# Power.net
KiCad netlist of a schematic drawn in Altium Designer
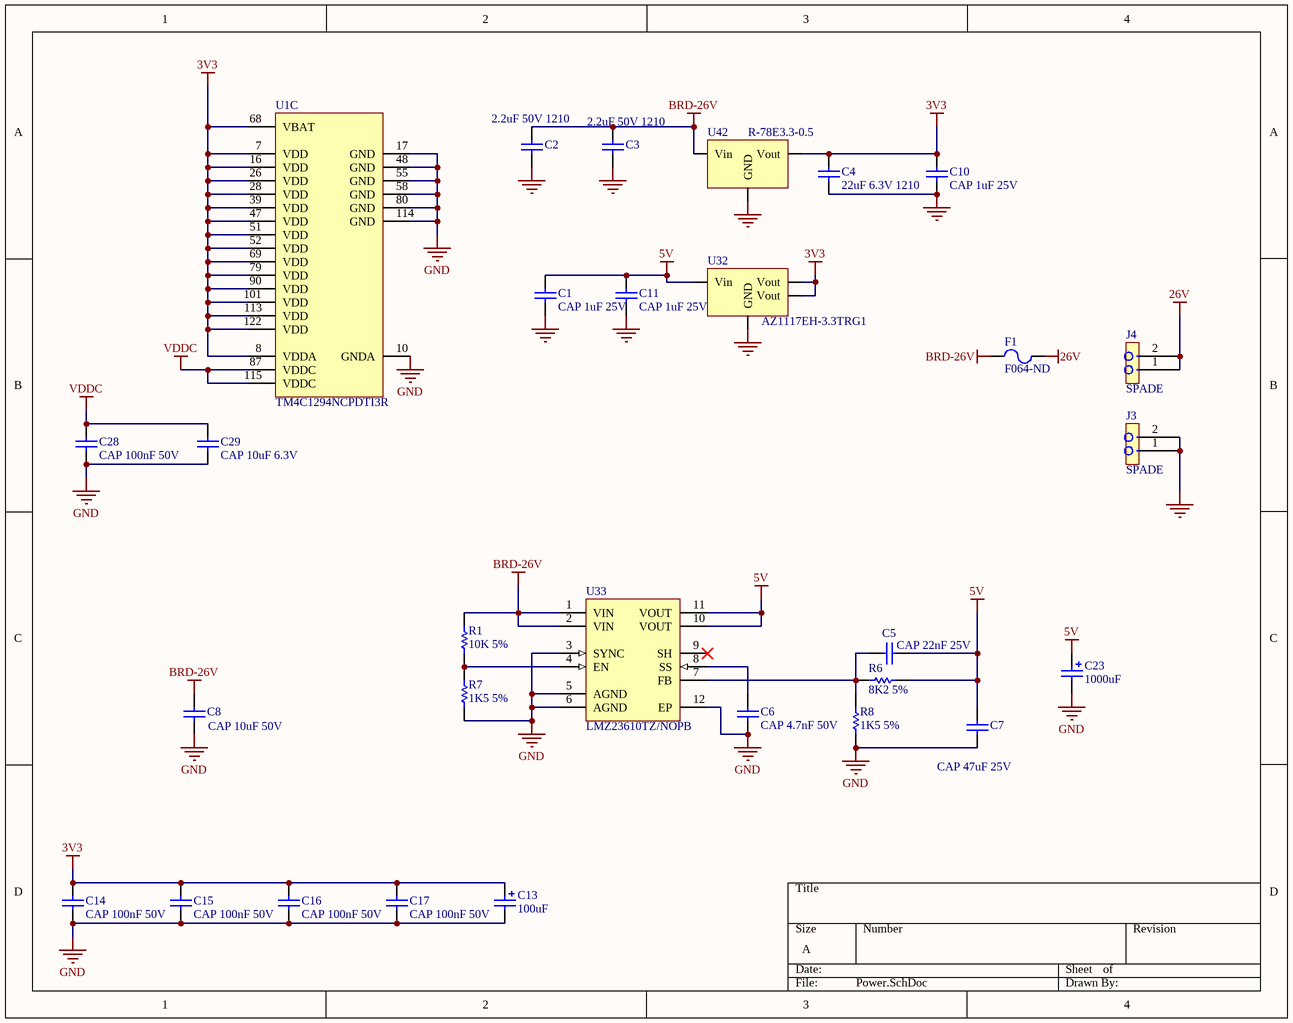
[diagram p0: Power.SchDoc]

(export (version "E")
  (design (tool "Eeschema 10.0.6"))
  (components
    (comp (ref "C1")
      (value "CAP 1uF 25V")
      (footprint "CAPC0603(1608)100_M")
      (description "CAP 1uF 25V Â±0.25pF 0603 (1608 Metric) Thickness 1mm SMD")
      (fields (field (name "TOLERANCE") "Â±0.25pF"))
      (libsource (lib "Altium Content Vault") (part "CMP-1035-00037-1"))
    )
    (comp (ref "C2")
      (value "2.2uF 50V 1210")
      (footprint "CAPC1210(3225)280_M")
      (description "CAP 2.2uF 50V ±20% 1210 (3225 Metric) Thickness 2.8mm SMD")
      (fields (field (name "TOLERANCE") "Â±20%"))
      (libsource (lib "Altium Content Vault") (part "CAP"))
    )
    (comp (ref "C3")
      (value "2.2uF 50V 1210")
      (footprint "CAPC1210(3225)280_M")
      (description "CAP 2.2uF 50V ±20% 1210 (3225 Metric) Thickness 2.8mm SMD")
      (fields (field (name "TOLERANCE") "Â±20%"))
      (libsource (lib "Altium Content Vault") (part "CAP"))
    )
    (comp (ref "C4")
      (value "22uF 6.3V 1210")
      (footprint "CAPC1210(3225)220_N")
      (description "CAP 22uF 6.3V ±10% 1210 (3225 Metric) Thickness 2.2mm SMD")
      (fields (field (name "TOLERANCE") "Â±10%"))
      (libsource (lib "Altium Content Vault") (part "CAP"))
    )
    (comp (ref "C5")
      (value "CAP 22nF 25V")
      (footprint "CAPC0805(2012)100_M")
      (description "CAP 22nF 25V Â±5% 0805 (2012 Metric) Thickness 1mm SMD")
      (fields (field (name "TOLERANCE") "Â±5%"))
      (libsource (lib "Altium Content Vault") (part "CMP-1036-04051-1"))
    )
    (comp (ref "C6")
      (value "CAP 4.7nF 50V")
      (footprint "CAPC0603(1608)100_M")
      (description "CAP 4.7nF 50V Â±20% 0603 (1608 Metric) Thickness 1mm SMD")
      (fields (field (name "TOLERANCE") "Â±20%"))
      (libsource (lib "Altium Content Vault") (part "CMP-1035-00333-1"))
    )
    (comp (ref "C7")
      (value "CAP 47uF 25V")
      (footprint "CAPC1206(3216)100_L")
      (description "CAP 47uF 25V Â±0.25pF 1206 (3216 Metric) Thickness 1mm SMD")
      (fields (field (name "TOLERANCE") "Â±0.25pF"))
      (libsource (lib "Altium Content Vault") (part "CMP-1037-00376-1"))
    )
    (comp (ref "C8")
      (value "CAP 10uF 50V")
      (footprint "CAPC1206(3216)190_M")
      (description "CAP 10uF 50V Â±10% 1206 (3216 Metric) Thickness 1.9mm SMD")
      (fields (field (name "TOLERANCE") "Â±10%"))
      (libsource (lib "Altium Content Vault") (part "CMP-1037-04982-1"))
    )
    (comp (ref "C10")
      (value "CAP 1uF 25V")
      (footprint "CAPC0603(1608)100_M")
      (description "CAP 1uF 25V Â±0.25pF 0603 (1608 Metric) Thickness 1mm SMD")
      (fields (field (name "TOLERANCE") "Â±0.25pF"))
      (libsource (lib "Altium Content Vault") (part "CMP-1035-00037-1"))
    )
    (comp (ref "C11")
      (value "CAP 1uF 25V")
      (footprint "CAPC0603(1608)100_M")
      (description "CAP 1uF 25V Â±0.25pF 0603 (1608 Metric) Thickness 1mm SMD")
      (fields (field (name "TOLERANCE") "Â±0.25pF"))
      (libsource (lib "Altium Content Vault") (part "CMP-1035-00037-1"))
    )
    (comp (ref "C13")
      (value "100uF")
      (footprint "PANASONIC_C")
      (description "Polarized Capacitor (Surface Mount)")
      (fields (field (name "PUBLISHER") "Altium Limited"))
      (libsource (lib "snarc+") (part "Cap_Polarized_100uF"))
    )
    (comp (ref "C14")
      (value "CAP 100nF 50V")
      (footprint "CAPC0603(1608)100_M")
      (description "CAP 100nF 50V Â±0.1pF 0603 (1608 Metric) Thickness 1mm SMD")
      (fields (field (name "TOLERANCE") "Â±0.1pF"))
      (libsource (lib "Altium Content Vault") (part "CMP-1035-00010-1"))
    )
    (comp (ref "C15")
      (value "CAP 100nF 50V")
      (footprint "CAPC0603(1608)100_M")
      (description "CAP 100nF 50V Â±0.1pF 0603 (1608 Metric) Thickness 1mm SMD")
      (fields (field (name "TOLERANCE") "Â±0.1pF"))
      (libsource (lib "Altium Content Vault") (part "CMP-1035-00010-1"))
    )
    (comp (ref "C16")
      (value "CAP 100nF 50V")
      (footprint "CAPC0603(1608)100_M")
      (description "CAP 100nF 50V Â±0.1pF 0603 (1608 Metric) Thickness 1mm SMD")
      (fields (field (name "TOLERANCE") "Â±0.1pF"))
      (libsource (lib "Altium Content Vault") (part "CMP-1035-00010-1"))
    )
    (comp (ref "C17")
      (value "CAP 100nF 50V")
      (footprint "CAPC0603(1608)100_M")
      (description "CAP 100nF 50V Â±0.1pF 0603 (1608 Metric) Thickness 1mm SMD")
      (fields (field (name "TOLERANCE") "Â±0.1pF"))
      (libsource (lib "Altium Content Vault") (part "CMP-1035-00010-1"))
    )
    (comp (ref "C23")
      (value "1000uF")
      (footprint "PANASONIC_H13")
      (description "Polarized Capacitor (Surface Mount)")
      (fields (field (name "PUBLISHER") "Altium Limited"))
      (libsource (lib "snarc+") (part "Cap_Polarized_1000uF"))
    )
    (comp (ref "C28")
      (value "CAP 100nF 50V")
      (footprint "CAPC0603(1608)100_M")
      (description "CAP 100nF 50V Â±0.1pF 0603 (1608 Metric) Thickness 1mm SMD")
      (fields (field (name "TOLERANCE") "Â±0.1pF"))
      (libsource (lib "Altium Content Vault") (part "CMP-1035-00010-1"))
    )
    (comp (ref "C29")
      (value "CAP 10uF 6.3V")
      (footprint "CAPC0603(1608)100_M")
      (description "CAP 10uF 6.3V ±10% 0603 (1608 Metric) Thickness 1mm SMD")
      (fields (field (name "TOLERANCE") "Â±10%"))
      (libsource (lib "Altium Content Vault") (part "CMP-1035-02796-1"))
    )
    (comp (ref "F1")
      (value "FUSE-2")
      (footprint "FUSE_HOLDER")
      (fields (field (name "SUPPLIER PART NUMBER 1") "F064-ND"))
      (libsource (lib "tankpower") (part "FUSE-2"))
    )
    (comp (ref "J3")
      (value "SPADE")
      (footprint "SPADE-6.35-RA")
      (description "6.35mm right-angle 90° male spade terminal PCB mount")
      (libsource (lib "HSBNE-Vend") (part "CON2"))
    )
    (comp (ref "J4")
      (value "SPADE")
      (footprint "SPADE-6.35-RA")
      (description "6.35mm right-angle 90° male spade terminal PCB mount")
      (libsource (lib "HSBNE-Vend") (part "CON2"))
    )
    (comp (ref "R1")
      (value "10K 5%")
      (footprint "RESC0603(1608)_M")
      (description "10K 0.1W 5% 0603 (1608 Metric)  SMD")
      (fields (field (name "TOLERANCE") "5 %") (field (name "POWER") "0.1 W"))
      (libsource (lib "Altium Content Vault") (part "CMP-1012-00098-1"))
    )
    (comp (ref "R6")
      (value "8K2 5%")
      (footprint "RESC0603(1608)_N")
      (description "8K2 0.1W 5% 0603 (1608 Metric)  SMD")
      (fields (field (name "TOLERANCE") "5 %") (field (name "POWER") "0.1 W"))
      (libsource (lib "Altium Content Vault") (part "RES"))
    )
    (comp (ref "R7")
      (value "1K5 5%")
      (footprint "RESC0603(1608)_M")
      (description "1K5 0.1W 5% 0603 (1608 Metric)  SMD")
      (fields (field (name "POWER") "0.1 W") (field (name "TOLERANCE") "5 %"))
      (libsource (lib "Altium Content Vault") (part "CMP-1012-00078-1"))
    )
    (comp (ref "R8")
      (value "1K5 5%")
      (footprint "RESC0603(1608)_M")
      (description "1K5 0.1W 5% 0603 (1608 Metric)  SMD")
      (fields (field (name "POWER") "0.1 W") (field (name "TOLERANCE") "5 %"))
      (libsource (lib "Altium Content Vault") (part "CMP-1012-00078-1"))
    )
    (comp (ref "U1")
      (value "TM4C1294NCPDTI3R")
      (footprint "TI-PDT128_M")
      (fields (field (name "MANUFACTURER") "Texas Instruments"))
      (libsource (lib "Altium Inc") (part "TI-TM4C1294NCPDT-128"))
    )
    (comp (ref "U32")
      (value "AZ1117EH-3.3TRG1")
      (footprint "SOT-223")
      (description "Reg 1A 3V3 OUT SIP VERT")
      (libsource (lib "HSBNE-Vend") (part "AZ1117EH"))
    )
    (comp (ref "U33")
      (value "LMZ23610TZ/NOPB")
      (footprint "NDY0011A_L")
      (fields (field (name "MANUFACTURER") "Texas Instruments"))
      (libsource (lib "Altium Content Vault") (part "PM-REG-LMZ23610-12"))
    )
    (comp (ref "U42")
      (value "R-78E3.3-0.5")
      (footprint "Buck_mod")
      (description "3V3 OUT SIP VERT")
      (libsource (lib "HSBNE-MAIN") (part "Buck 3V3 OUT SIP VERT"))
    )
  )
  (nets
    (net (code "1") (name "3V3") (class "Default")
      (node (ref "C10") (pin "2") (pinfunction "2_2") (pintype "passive"))
      (node (ref "C13") (pin "+") (pinfunction "+_+") (pintype "passive"))
      (node (ref "C14") (pin "2") (pinfunction "2_2") (pintype "passive"))
      (node (ref "C15") (pin "2") (pinfunction "2_2") (pintype "passive"))
      (node (ref "C16") (pin "2") (pinfunction "2_2") (pintype "passive"))
      (node (ref "C17") (pin "2") (pinfunction "2_2") (pintype "passive"))
      (node (ref "C4") (pin "2") (pinfunction "2_2") (pintype "passive"))
      (node (ref "U1") (pin "101") (pinfunction "VDD_101") (pintype "power_in"))
      (node (ref "U1") (pin "113") (pinfunction "VDD_113") (pintype "power_in"))
      (node (ref "U1") (pin "122") (pinfunction "VDD_122") (pintype "power_in"))
      (node (ref "U1") (pin "16") (pinfunction "VDD_16") (pintype "power_in"))
      (node (ref "U1") (pin "26") (pinfunction "VDD_26") (pintype "power_in"))
      (node (ref "U1") (pin "28") (pinfunction "VDD_28") (pintype "power_in"))
      (node (ref "U1") (pin "39") (pinfunction "VDD_39") (pintype "power_in"))
      (node (ref "U1") (pin "47") (pinfunction "VDD_47") (pintype "power_in"))
      (node (ref "U1") (pin "51") (pinfunction "VDD_51") (pintype "power_in"))
      (node (ref "U1") (pin "52") (pinfunction "VDD_52") (pintype "power_in"))
      (node (ref "U1") (pin "68") (pinfunction "VBAT_68") (pintype "power_in"))
      (node (ref "U1") (pin "69") (pinfunction "VDD_69") (pintype "power_in"))
      (node (ref "U1") (pin "7") (pinfunction "VDD_7") (pintype "power_in"))
      (node (ref "U1") (pin "79") (pinfunction "VDD_79") (pintype "power_in"))
      (node (ref "U1") (pin "8") (pinfunction "VDDA_8") (pintype "power_in"))
      (node (ref "U1") (pin "90") (pinfunction "VDD_90") (pintype "power_in"))
      (node (ref "U32") (pin "2") (pinfunction "Vout_2") (pintype "power_in"))
      (node (ref "U32") (pin "4") (pinfunction "Vout_4") (pintype "power_in"))
      (node (ref "U42") (pin "3") (pinfunction "Vout_3") (pintype "power_in"))
    )
    (net (code "2") (name "5V") (class "Default")
      (node (ref "C1") (pin "2") (pinfunction "2_2") (pintype "passive"))
      (node (ref "C11") (pin "2") (pinfunction "2_2") (pintype "passive"))
      (node (ref "C23") (pin "+") (pinfunction "+_+") (pintype "passive"))
      (node (ref "C5") (pin "2") (pinfunction "2_2") (pintype "passive"))
      (node (ref "C7") (pin "1") (pinfunction "1_1") (pintype "passive"))
      (node (ref "R6") (pin "1") (pinfunction "1_1") (pintype "passive"))
      (node (ref "U32") (pin "3") (pinfunction "Vin_3") (pintype "power_in"))
      (node (ref "U33") (pin "10") (pinfunction "VOUT_10") (pintype "power_in"))
      (node (ref "U33") (pin "11") (pinfunction "VOUT_11") (pintype "power_in"))
    )
    (net (code "3") (name "26V") (class "Default")
      (node (ref "F1") (pin "1") (pinfunction "1_1") (pintype "passive"))
      (node (ref "J4") (pin "1") (pintype "passive"))
      (node (ref "J4") (pin "2") (pintype "passive"))
    )
    (net (code "4") (name "BRD-26V") (class "Default")
      (node (ref "C2") (pin "2") (pinfunction "2_2") (pintype "passive"))
      (node (ref "C3") (pin "2") (pinfunction "2_2") (pintype "passive"))
      (node (ref "C8") (pin "1") (pinfunction "1_1") (pintype "passive"))
      (node (ref "F1") (pin "2") (pinfunction "2_2") (pintype "passive"))
      (node (ref "R1") (pin "2") (pinfunction "2_2") (pintype "passive"))
      (node (ref "U33") (pin "1") (pinfunction "VIN_1") (pintype "power_in"))
      (node (ref "U33") (pin "2") (pinfunction "VIN_2") (pintype "power_in"))
      (node (ref "U42") (pin "1") (pinfunction "Vin_1") (pintype "power_in"))
    )
    (net (code "5") (name "GND") (class "Default")
      (node (ref "C1") (pin "1") (pinfunction "1_1") (pintype "passive"))
      (node (ref "C10") (pin "1") (pinfunction "1_1") (pintype "passive"))
      (node (ref "C11") (pin "1") (pinfunction "1_1") (pintype "passive"))
      (node (ref "C13") (pin "-") (pinfunction "-_-") (pintype "passive"))
      (node (ref "C14") (pin "1") (pinfunction "1_1") (pintype "passive"))
      (node (ref "C15") (pin "1") (pinfunction "1_1") (pintype "passive"))
      (node (ref "C16") (pin "1") (pinfunction "1_1") (pintype "passive"))
      (node (ref "C17") (pin "1") (pinfunction "1_1") (pintype "passive"))
      (node (ref "C2") (pin "1") (pinfunction "1_1") (pintype "passive"))
      (node (ref "C23") (pin "-") (pinfunction "-_-") (pintype "passive"))
      (node (ref "C28") (pin "1") (pinfunction "1_1") (pintype "passive"))
      (node (ref "C29") (pin "1") (pinfunction "1_1") (pintype "passive"))
      (node (ref "C3") (pin "1") (pinfunction "1_1") (pintype "passive"))
      (node (ref "C4") (pin "1") (pinfunction "1_1") (pintype "passive"))
      (node (ref "C6") (pin "1") (pinfunction "1_1") (pintype "passive"))
      (node (ref "C7") (pin "2") (pinfunction "2_2") (pintype "passive"))
      (node (ref "C8") (pin "2") (pinfunction "2_2") (pintype "passive"))
      (node (ref "J3") (pin "1") (pintype "passive"))
      (node (ref "J3") (pin "2") (pintype "passive"))
      (node (ref "R7") (pin "1") (pinfunction "1_1") (pintype "passive"))
      (node (ref "R8") (pin "1") (pinfunction "1_1") (pintype "passive"))
      (node (ref "U1") (pin "10") (pinfunction "GNDA_10") (pintype "power_in"))
      (node (ref "U1") (pin "114") (pinfunction "GND_114") (pintype "power_in"))
      (node (ref "U1") (pin "17") (pinfunction "GND_17") (pintype "power_in"))
      (node (ref "U1") (pin "48") (pinfunction "GND_48") (pintype "power_in"))
      (node (ref "U1") (pin "55") (pinfunction "GND_55") (pintype "power_in"))
      (node (ref "U1") (pin "58") (pinfunction "GND_58") (pintype "power_in"))
      (node (ref "U1") (pin "80") (pinfunction "GND_80") (pintype "power_in"))
      (node (ref "U32") (pin "1") (pinfunction "GND_1") (pintype "power_in"))
      (node (ref "U33") (pin "12") (pinfunction "EP_12") (pintype "power_in"))
      (node (ref "U33") (pin "3") (pinfunction "SYNC_3") (pintype "input"))
      (node (ref "U33") (pin "5") (pinfunction "AGND_5") (pintype "power_in"))
      (node (ref "U33") (pin "6") (pinfunction "AGND_6") (pintype "power_in"))
      (node (ref "U42") (pin "2") (pinfunction "GND_2") (pintype "power_in"))
    )
    (net (code "6") (name "Net-(U33-EN)") (class "Default")
      (node (ref "R1") (pin "1") (pinfunction "1_1") (pintype "passive"))
      (node (ref "R7") (pin "2") (pinfunction "2_2") (pintype "passive"))
      (node (ref "U33") (pin "4") (pinfunction "EN_4") (pintype "input"))
    )
    (net (code "7") (name "Net-(U33-FB)") (class "Default")
      (node (ref "C5") (pin "1") (pinfunction "1_1") (pintype "passive"))
      (node (ref "R6") (pin "2") (pinfunction "2_2") (pintype "passive"))
      (node (ref "R8") (pin "2") (pinfunction "2_2") (pintype "passive"))
      (node (ref "U33") (pin "7") (pinfunction "FB_7") (pintype "passive"))
    )
    (net (code "8") (name "Net-(U33-SS)") (class "Default")
      (node (ref "C6") (pin "2") (pinfunction "2_2") (pintype "passive"))
      (node (ref "U33") (pin "8") (pinfunction "SS_8") (pintype "input"))
    )
    (net (code "9") (name "VDDC") (class "Default")
      (node (ref "C28") (pin "2") (pinfunction "2_2") (pintype "passive"))
      (node (ref "C29") (pin "2") (pinfunction "2_2") (pintype "passive"))
      (node (ref "U1") (pin "115") (pinfunction "VDDC_115") (pintype "power_in"))
      (node (ref "U1") (pin "87") (pinfunction "VDDC_87") (pintype "power_in"))
    )
    (net (code "10") (name "unconnected-(U33-SH-Pad9)") (class "Default")
      (node (ref "U33") (pin "9") (pinfunction "SH_9") (pintype "passive+no_connect"))
    )
  )
)
